# SCH_usb-hub.net
KiCad netlist of a schematic drawn in EasyEDA
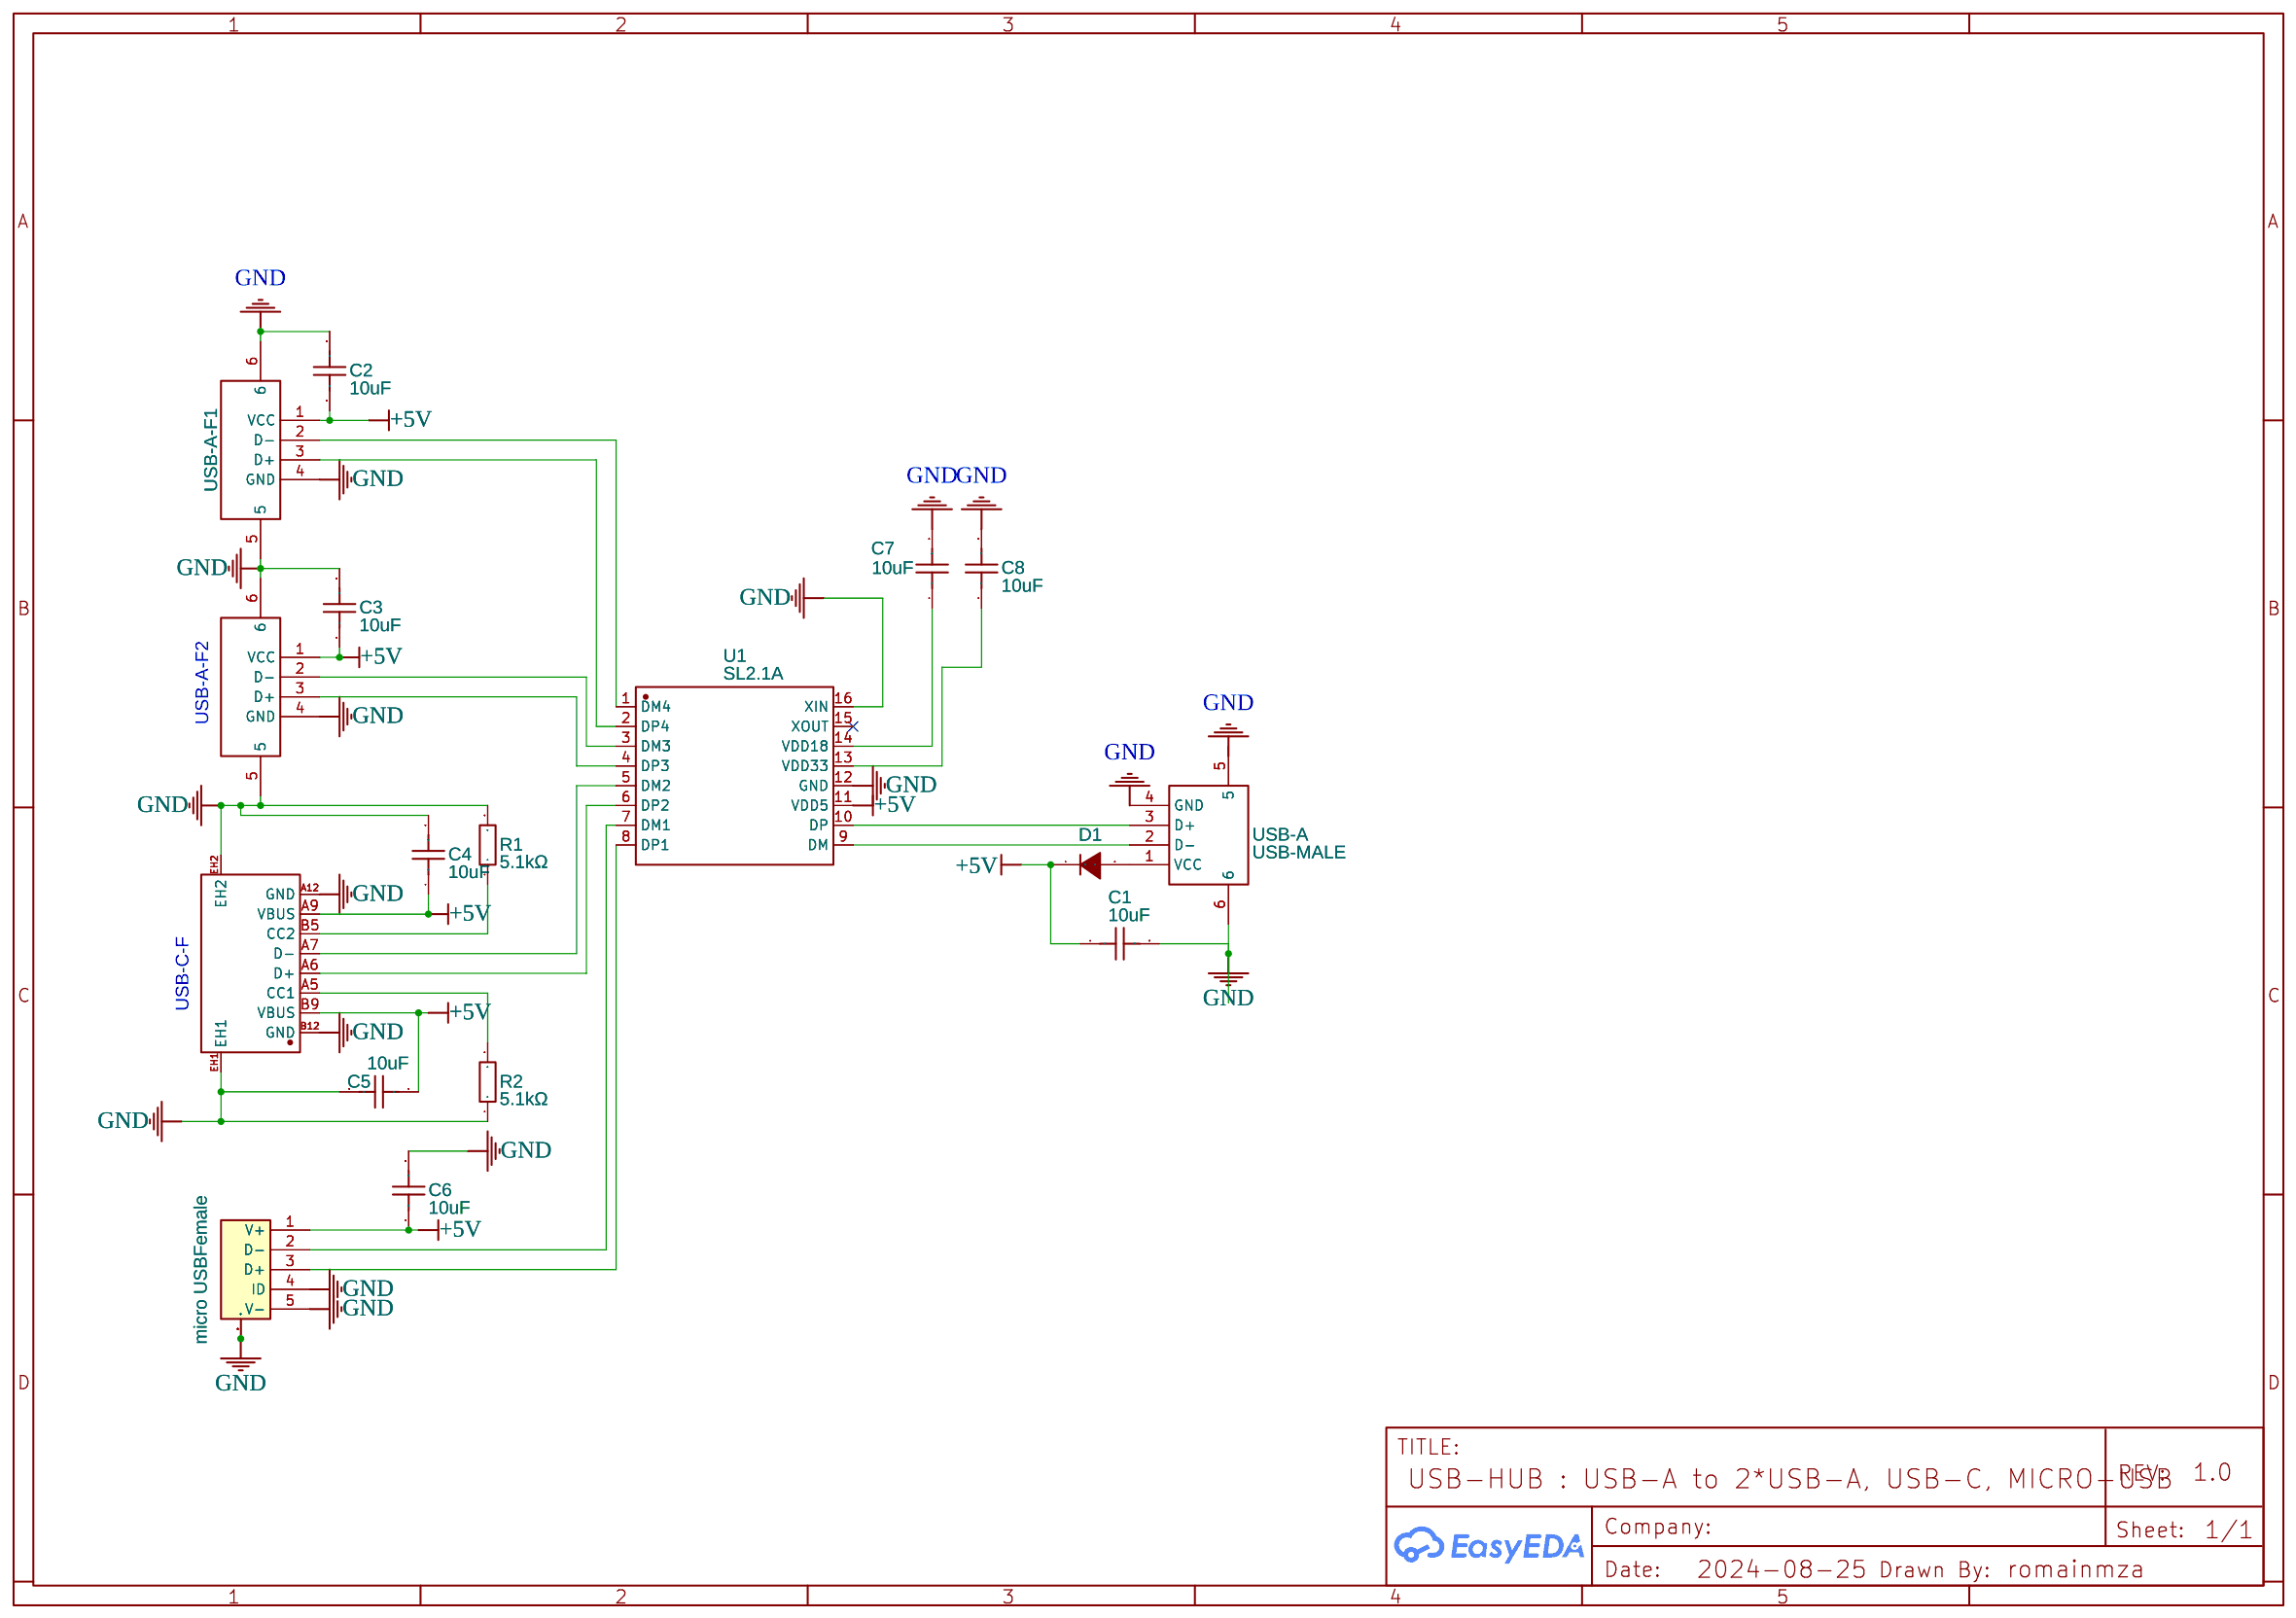
[diagram p0: schematic sheet]

(export (version "E")
  (design (tool "Eeschema 10.0.6"))
  (components
    (comp (ref "C1")
      (value "10uF")
      (fields
        (field (name "Manufacturer Part") "CL10A106KP8NNNC")
        (field (name "Manufacturer") "SAMSUNG(三星)")
      )
      (libsource (lib "") (part "CL10A106KP8NNNC_2"))
    )
    (comp (ref "C2")
      (value "10uF")
      (fields
        (field (name "Manufacturer Part") "CL10A106KP8NNNC")
        (field (name "Manufacturer") "SAMSUNG(三星)")
      )
      (libsource (lib "") (part "CL10A106KP8NNNC"))
    )
    (comp (ref "C3")
      (value "10uF")
      (fields
        (field (name "Manufacturer Part") "CL10A106KP8NNNC")
        (field (name "Manufacturer") "SAMSUNG(三星)")
      )
      (libsource (lib "") (part "CL10A106KP8NNNC"))
    )
    (comp (ref "C4")
      (value "10uF")
      (fields
        (field (name "Manufacturer Part") "CL10A106KP8NNNC")
        (field (name "Manufacturer") "SAMSUNG(三星)")
      )
      (libsource (lib "") (part "CL10A106KP8NNNC"))
    )
    (comp (ref "C5")
      (value "10uF")
      (fields
        (field (name "Manufacturer Part") "CL10A106KP8NNNC")
        (field (name "Manufacturer") "SAMSUNG(三星)")
      )
      (libsource (lib "") (part "CL10A106KP8NNNC_1"))
    )
    (comp (ref "C6")
      (value "10uF")
      (fields
        (field (name "Manufacturer Part") "CL10A106KP8NNNC")
        (field (name "Manufacturer") "SAMSUNG(三星)")
      )
      (libsource (lib "") (part "CL10A106KP8NNNC"))
    )
    (comp (ref "C7")
      (value "10uF")
      (fields
        (field (name "Manufacturer Part") "CL10A106KP8NNNC")
        (field (name "Manufacturer") "SAMSUNG(三星)")
      )
      (libsource (lib "") (part "CL10A106KP8NNNC"))
    )
    (comp (ref "C8")
      (value "10uF")
      (fields
        (field (name "Manufacturer Part") "CL10A106KP8NNNC")
        (field (name "Manufacturer") "SAMSUNG(三星)")
      )
      (libsource (lib "") (part "CL10A106KP8NNNC"))
    )
    (comp (ref "D1")
      (value "NSR0320MW2T1G")
      (fields (field (name "Manufacturer") "onsemi(安森美)"))
      (libsource (lib "") (part "NSR0320MW2T1G"))
    )
    (comp (ref "R1")
      (value "5.1kΩ")
      (fields
        (field (name "Manufacturer Part") "0402WGF5101TCE")
        (field (name "Manufacturer") "UNI-ROYAL(厚声)")
      )
      (libsource (lib "") (part "0402WGF5101TCE"))
    )
    (comp (ref "R2")
      (value "5.1kΩ")
      (fields
        (field (name "Manufacturer Part") "0402WGF5101TCE")
        (field (name "Manufacturer") "UNI-ROYAL(厚声)")
      )
      (libsource (lib "") (part "0402WGF5101TCE"))
    )
    (comp (ref "U1")
      (value "SL2.1A")
      (fields (field (name "Manufacturer") "CoreChips(和芯润德)"))
      (libsource (lib "") (part "SL2.1A"))
    )
    (comp (ref "USB-A")
      (value "USB-MALE")
      (fields (field (name "Manufacturer Part") "U-G-O4DD-W-1") (field (name "Manufacturer") "韩国韩荣"))
      (libsource (lib "") (part "U-G-04DD-W-01"))
    )
    (comp (ref "USB-A-F1")
      (value "AF-90")
      (fields (field (name "Manufacturer Part") "903-131A1011D10100") (field (name "Manufacturer") "精拓金"))
      (libsource (lib "") (part "USB-AF-90-14.4X13.6-H7.0-DIP"))
    )
    (comp (ref "USB1")
      (value "micro USBFemale")
      (fields (field (name "Manufacturer Part") "920-E52A2021S10100") (field (name "Manufacturer") "精拓金"))
      (libsource (lib "") (part "micro USBFemale"))
    )
    (comp (ref "USB2")
      (value "GT-USB-7100A")
      (fields (field (name "Manufacturer") "G-Switch(品赞)"))
      (libsource (lib "") (part "GT-USB-7100A"))
    )
    (comp (ref "USB3")
      (value "AF-90")
      (fields (field (name "Manufacturer Part") "903-131A1011D10100") (field (name "Manufacturer") "精拓金"))
      (libsource (lib "") (part "USB-AF-90-14.4X13.6-H7.0-DIP_1"))
    )
  )
  (nets
    (net (code "1") (name "+5V") (class "Default")
      (node (ref "C1") (pin "1") (pinfunction "1_1") (pintype "unspecified"))
      (node (ref "C2") (pin "1") (pinfunction "1_1") (pintype "unspecified"))
      (node (ref "C3") (pin "1") (pinfunction "1_1") (pintype "unspecified"))
      (node (ref "C4") (pin "1") (pinfunction "1_1") (pintype "unspecified"))
      (node (ref "C5") (pin "1") (pinfunction "1_1") (pintype "unspecified"))
      (node (ref "C6") (pin "1") (pinfunction "1_1") (pintype "unspecified"))
      (node (ref "D1") (pin "1") (pinfunction "C_1") (pintype "unspecified"))
      (node (ref "U1") (pin "11") (pinfunction "VDD5_11") (pintype "unspecified"))
      (node (ref "USB-A-F1") (pin "1") (pinfunction "VCC_1") (pintype "unspecified"))
      (node (ref "USB1") (pin "1") (pinfunction "V+_1") (pintype "unspecified"))
      (node (ref "USB2") (pin "A9") (pinfunction "VBUS_A9") (pintype "unspecified"))
      (node (ref "USB2") (pin "B9") (pinfunction "VBUS_B9") (pintype "unspecified"))
      (node (ref "USB3") (pin "1") (pinfunction "VCC_1") (pintype "unspecified"))
    )
    (net (code "2") (name "GND") (class "Default")
      (node (ref "C1") (pin "2") (pinfunction "2_2") (pintype "unspecified"))
      (node (ref "C2") (pin "2") (pinfunction "2_2") (pintype "unspecified"))
      (node (ref "C3") (pin "2") (pinfunction "2_2") (pintype "unspecified"))
      (node (ref "C4") (pin "2") (pinfunction "2_2") (pintype "unspecified"))
      (node (ref "C5") (pin "2") (pinfunction "2_2") (pintype "unspecified"))
      (node (ref "C6") (pin "2") (pinfunction "2_2") (pintype "unspecified"))
      (node (ref "C7") (pin "2") (pinfunction "2_2") (pintype "unspecified"))
      (node (ref "C8") (pin "2") (pinfunction "2_2") (pintype "unspecified"))
      (node (ref "R1") (pin "2") (pinfunction "2_2") (pintype "input"))
      (node (ref "R2") (pin "1") (pinfunction "1_1") (pintype "input"))
      (node (ref "U1") (pin "12") (pinfunction "GND_12") (pintype "unspecified"))
      (node (ref "U1") (pin "16") (pinfunction "XIN_16") (pintype "unspecified"))
      (node (ref "USB-A") (pin "4") (pinfunction "GND_4") (pintype "unspecified"))
      (node (ref "USB-A") (pin "5") (pinfunction "5_5") (pintype "unspecified"))
      (node (ref "USB-A") (pin "6") (pinfunction "6_6") (pintype "unspecified"))
      (node (ref "USB-A-F1") (pin "4") (pinfunction "GND_4") (pintype "unspecified"))
      (node (ref "USB-A-F1") (pin "5") (pinfunction "5_5") (pintype "unspecified"))
      (node (ref "USB-A-F1") (pin "6") (pinfunction "6_6") (pintype "unspecified"))
      (node (ref "USB1") (pin "4") (pinfunction "ID_4") (pintype "unspecified"))
      (node (ref "USB1") (pin "5") (pinfunction "V-_5") (pintype "unspecified"))
      (node (ref "USB1") (pin "SH0") (pinfunction "MTN_SH0") (pintype "input"))
      (node (ref "USB1") (pin "SH1") (pinfunction "1_SH1") (pintype "unspecified"))
      (node (ref "USB1") (pin "SH2") (pinfunction "2_SH2") (pintype "unspecified"))
      (node (ref "USB1") (pin "SH3") (pinfunction "3_SH3") (pintype "unspecified"))
      (node (ref "USB2") (pin "A12") (pinfunction "GND_A12") (pintype "unspecified"))
      (node (ref "USB2") (pin "B12") (pinfunction "GND_B12") (pintype "unspecified"))
      (node (ref "USB2") (pin "EH1") (pinfunction "EH1_EH1") (pintype "unspecified"))
      (node (ref "USB2") (pin "EH2") (pinfunction "EH2_EH2") (pintype "unspecified"))
      (node (ref "USB3") (pin "4") (pinfunction "GND_4") (pintype "unspecified"))
      (node (ref "USB3") (pin "5") (pinfunction "5_5") (pintype "unspecified"))
      (node (ref "USB3") (pin "6") (pinfunction "6_6") (pintype "unspecified"))
    )
    (net (code "3") (name "Net-(D1-A)") (class "Default")
      (node (ref "D1") (pin "2") (pinfunction "A_2") (pintype "unspecified"))
      (node (ref "USB-A") (pin "1") (pinfunction "VCC_1") (pintype "unspecified"))
    )
    (net (code "4") (name "Net-(U1-DM)") (class "Default")
      (node (ref "U1") (pin "9") (pinfunction "DM_9") (pintype "unspecified"))
      (node (ref "USB-A") (pin "2") (pinfunction "D-_2") (pintype "unspecified"))
    )
    (net (code "5") (name "Net-(U1-DM1)") (class "Default")
      (node (ref "U1") (pin "7") (pinfunction "DM1_7") (pintype "unspecified"))
      (node (ref "USB1") (pin "2") (pinfunction "D-_2") (pintype "unspecified"))
    )
    (net (code "6") (name "Net-(U1-DM2)") (class "Default")
      (node (ref "U1") (pin "5") (pinfunction "DM2_5") (pintype "unspecified"))
      (node (ref "USB2") (pin "A7") (pinfunction "D-_A7") (pintype "unspecified"))
    )
    (net (code "7") (name "Net-(U1-DM3)") (class "Default")
      (node (ref "U1") (pin "3") (pinfunction "DM3_3") (pintype "unspecified"))
      (node (ref "USB3") (pin "2") (pinfunction "D-_2") (pintype "unspecified"))
    )
    (net (code "8") (name "Net-(U1-DM4)") (class "Default")
      (node (ref "U1") (pin "1") (pinfunction "DM4_1") (pintype "unspecified"))
      (node (ref "USB-A-F1") (pin "2") (pinfunction "D-_2") (pintype "unspecified"))
    )
    (net (code "9") (name "Net-(U1-DP)") (class "Default")
      (node (ref "U1") (pin "10") (pinfunction "DP_10") (pintype "unspecified"))
      (node (ref "USB-A") (pin "3") (pinfunction "D+_3") (pintype "unspecified"))
    )
    (net (code "10") (name "Net-(U1-DP1)") (class "Default")
      (node (ref "U1") (pin "8") (pinfunction "DP1_8") (pintype "unspecified"))
      (node (ref "USB1") (pin "3") (pinfunction "D+_3") (pintype "unspecified"))
    )
    (net (code "11") (name "Net-(U1-DP2)") (class "Default")
      (node (ref "U1") (pin "6") (pinfunction "DP2_6") (pintype "unspecified"))
      (node (ref "USB2") (pin "A6") (pinfunction "D+_A6") (pintype "unspecified"))
    )
    (net (code "12") (name "Net-(U1-DP3)") (class "Default")
      (node (ref "U1") (pin "4") (pinfunction "DP3_4") (pintype "unspecified"))
      (node (ref "USB3") (pin "3") (pinfunction "D+_3") (pintype "unspecified"))
    )
    (net (code "13") (name "Net-(U1-DP4)") (class "Default")
      (node (ref "U1") (pin "2") (pinfunction "DP4_2") (pintype "unspecified"))
      (node (ref "USB-A-F1") (pin "3") (pinfunction "D+_3") (pintype "unspecified"))
    )
    (net (code "14") (name "Net-(U1-VDD18)") (class "Default")
      (node (ref "C7") (pin "1") (pinfunction "1_1") (pintype "unspecified"))
      (node (ref "U1") (pin "14") (pinfunction "VDD18_14") (pintype "unspecified"))
    )
    (net (code "15") (name "Net-(U1-VDD33)") (class "Default")
      (node (ref "C8") (pin "1") (pinfunction "1_1") (pintype "unspecified"))
      (node (ref "U1") (pin "13") (pinfunction "VDD33_13") (pintype "unspecified"))
    )
    (net (code "16") (name "Net-(USB2-CC1)") (class "Default")
      (node (ref "R2") (pin "2") (pinfunction "2_2") (pintype "input"))
      (node (ref "USB2") (pin "A5") (pinfunction "CC1_A5") (pintype "unspecified"))
    )
    (net (code "17") (name "Net-(USB2-CC2)") (class "Default")
      (node (ref "R1") (pin "1") (pinfunction "1_1") (pintype "input"))
      (node (ref "USB2") (pin "B5") (pinfunction "CC2_B5") (pintype "unspecified"))
    )
    (net (code "18") (name "unconnected-(U1-XOUT-Pad15)") (class "Default")
      (node (ref "U1") (pin "15") (pinfunction "XOUT_15") (pintype "unspecified+no_connect"))
    )
  )
)
